# Breakout_Board.net
KiCad netlist of a schematic drawn in EAGLE
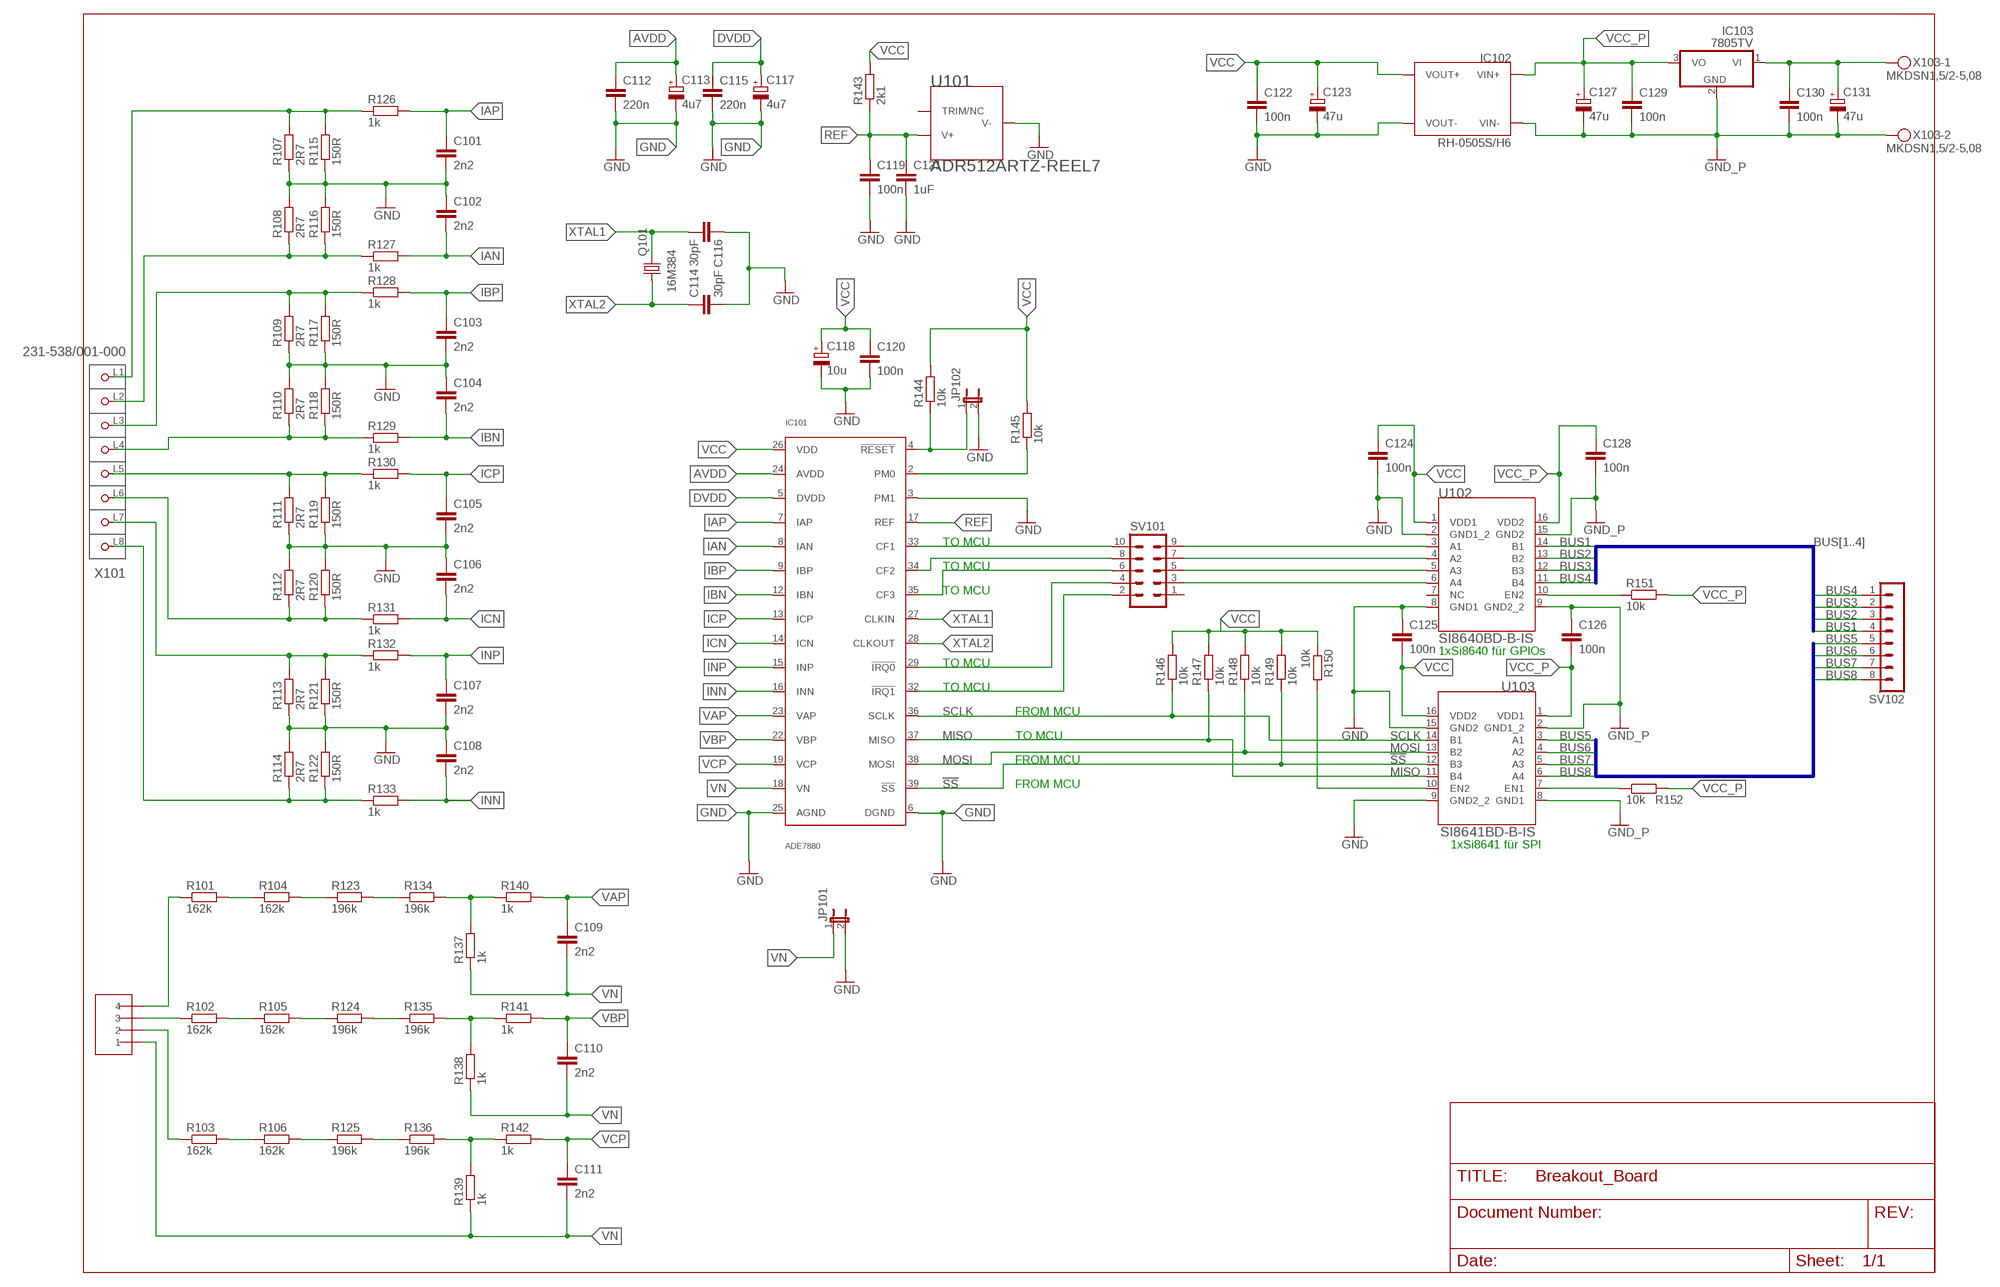
[diagram p0: schematic, sheet 1]

(export (version "E")
  (design (tool "Eeschema 10.0.6"))
  (components
    (comp (ref "C101")
      (value "2n2")
      (footprint "eagle-import:C0603K")
      (libsource (lib "eagle-import") (part "C-EUC0603K"))
    )
    (comp (ref "C102")
      (value "2n2")
      (footprint "eagle-import:C0603K")
      (libsource (lib "eagle-import") (part "C-EUC0603K"))
    )
    (comp (ref "C103")
      (value "2n2")
      (footprint "eagle-import:C0603K")
      (libsource (lib "eagle-import") (part "C-EUC0603K"))
    )
    (comp (ref "C104")
      (value "2n2")
      (footprint "eagle-import:C0603K")
      (libsource (lib "eagle-import") (part "C-EUC0603K"))
    )
    (comp (ref "C105")
      (value "2n2")
      (footprint "eagle-import:C0603K")
      (libsource (lib "eagle-import") (part "C-EUC0603K"))
    )
    (comp (ref "C106")
      (value "2n2")
      (footprint "eagle-import:C0603K")
      (libsource (lib "eagle-import") (part "C-EUC0603K"))
    )
    (comp (ref "C107")
      (value "2n2")
      (footprint "eagle-import:C0603K")
      (libsource (lib "eagle-import") (part "C-EUC0603K"))
    )
    (comp (ref "C108")
      (value "2n2")
      (footprint "eagle-import:C0603K")
      (libsource (lib "eagle-import") (part "C-EUC0603K"))
    )
    (comp (ref "C109")
      (value "2n2")
      (footprint "eagle-import:C0603K")
      (libsource (lib "eagle-import") (part "C-EUC0603K"))
    )
    (comp (ref "C110")
      (value "2n2")
      (footprint "eagle-import:C0603K")
      (libsource (lib "eagle-import") (part "C-EUC0603K"))
    )
    (comp (ref "C111")
      (value "2n2")
      (footprint "eagle-import:C0603K")
      (libsource (lib "eagle-import") (part "C-EUC0603K"))
    )
    (comp (ref "C112")
      (value "220n")
      (footprint "eagle-import:C0603K")
      (libsource (lib "eagle-import") (part "C-EUC0603K"))
    )
    (comp (ref "C113")
      (value "4u7")
      (footprint "eagle-import:PANASONIC_B")
      (libsource (lib "eagle-import") (part "CPOL-EUB"))
    )
    (comp (ref "C114")
      (value "30pF")
      (footprint "eagle-import:C0603K")
      (libsource (lib "eagle-import") (part "C-EUC0603K"))
    )
    (comp (ref "C115")
      (value "220n")
      (footprint "eagle-import:C0603K")
      (libsource (lib "eagle-import") (part "C-EUC0603K"))
    )
    (comp (ref "C116")
      (value "30pF")
      (footprint "eagle-import:C0603K")
      (libsource (lib "eagle-import") (part "C-EUC0603K"))
    )
    (comp (ref "C117")
      (value "4u7")
      (footprint "eagle-import:PANASONIC_B")
      (libsource (lib "eagle-import") (part "CPOL-EUB"))
    )
    (comp (ref "C118")
      (value "10u")
      (footprint "eagle-import:PANASONIC_B")
      (libsource (lib "eagle-import") (part "CPOL-EUB"))
    )
    (comp (ref "C119")
      (value "100n")
      (footprint "eagle-import:C0603K")
      (libsource (lib "eagle-import") (part "C-EUC0603K"))
    )
    (comp (ref "C120")
      (value "100n")
      (footprint "eagle-import:C0603K")
      (libsource (lib "eagle-import") (part "C-EUC0603K"))
    )
    (comp (ref "C121")
      (value "1uF")
      (footprint "eagle-import:C0603K")
      (libsource (lib "eagle-import") (part "C-EUC0603K"))
    )
    (comp (ref "C122")
      (value "100n")
      (footprint "eagle-import:C0603K")
      (libsource (lib "eagle-import") (part "C-EUC0603K"))
    )
    (comp (ref "C123")
      (value "47u")
      (footprint "eagle-import:PANASONIC_D")
      (libsource (lib "eagle-import") (part "CPOL-EUD"))
    )
    (comp (ref "C124")
      (value "100n")
      (footprint "eagle-import:C0603K")
      (libsource (lib "eagle-import") (part "C-EUC0603K"))
    )
    (comp (ref "C125")
      (value "100n")
      (footprint "eagle-import:C0603K")
      (libsource (lib "eagle-import") (part "C-EUC0603K"))
    )
    (comp (ref "C126")
      (value "100n")
      (footprint "eagle-import:C0603K")
      (libsource (lib "eagle-import") (part "C-EUC0603K"))
    )
    (comp (ref "C127")
      (value "47u")
      (footprint "eagle-import:PANASONIC_D")
      (libsource (lib "eagle-import") (part "CPOL-EUD"))
    )
    (comp (ref "C128")
      (value "100n")
      (footprint "eagle-import:C0603K")
      (libsource (lib "eagle-import") (part "C-EUC0603K"))
    )
    (comp (ref "C129")
      (value "100n")
      (footprint "eagle-import:C0603K")
      (libsource (lib "eagle-import") (part "C-EUC0603K"))
    )
    (comp (ref "C130")
      (value "100n")
      (footprint "eagle-import:C0603K")
      (libsource (lib "eagle-import") (part "C-EUC0603K"))
    )
    (comp (ref "C131")
      (value "47u")
      (footprint "eagle-import:PANASONIC_D")
      (libsource (lib "eagle-import") (part "CPOL-EUD"))
    )
    (comp (ref "IC101")
      (value "ADE7880")
      (footprint "eagle-import:BREAKOUT40P")
      (libsource (lib "eagle-import") (part "ADE7880"))
    )
    (comp (ref "IC102")
      (value "RH-0505S/H6")
      (footprint "eagle-import:RH_H6")
      (libsource (lib "eagle-import") (part "RH-0505S/H6"))
    )
    (comp (ref "IC103")
      (value "7805TV")
      (footprint "eagle-import:TO220V")
      (libsource (lib "eagle-import") (part "78TV05"))
    )
    (comp (ref "JP101")
      (value "JP1E")
      (footprint "eagle-import:JP1")
      (libsource (lib "eagle-import") (part "JP1E"))
    )
    (comp (ref "JP102")
      (value "JP1E")
      (footprint "eagle-import:JP1")
      (libsource (lib "eagle-import") (part "JP1E"))
    )
    (comp (ref "Q101")
      (value "16M384")
      (footprint "eagle-import:HC49UP")
      (libsource (lib "eagle-import") (part "CRYSTALHC49UP"))
    )
    (comp (ref "R101")
      (value "162k")
      (footprint "eagle-import:R0805")
      (libsource (lib "eagle-import") (part "R-EU_R0805"))
    )
    (comp (ref "R102")
      (value "162k")
      (footprint "eagle-import:R0805")
      (libsource (lib "eagle-import") (part "R-EU_R0805"))
    )
    (comp (ref "R103")
      (value "162k")
      (footprint "eagle-import:R0805")
      (libsource (lib "eagle-import") (part "R-EU_R0805"))
    )
    (comp (ref "R104")
      (value "162k")
      (footprint "eagle-import:R0805")
      (libsource (lib "eagle-import") (part "R-EU_R0805"))
    )
    (comp (ref "R105")
      (value "162k")
      (footprint "eagle-import:R0805")
      (libsource (lib "eagle-import") (part "R-EU_R0805"))
    )
    (comp (ref "R106")
      (value "162k")
      (footprint "eagle-import:R0805")
      (libsource (lib "eagle-import") (part "R-EU_R0805"))
    )
    (comp (ref "R107")
      (value "2R7")
      (footprint "eagle-import:R0805")
      (libsource (lib "eagle-import") (part "R-EU_R0805"))
    )
    (comp (ref "R108")
      (value "2R7")
      (footprint "eagle-import:R0805")
      (libsource (lib "eagle-import") (part "R-EU_R0805"))
    )
    (comp (ref "R109")
      (value "2R7")
      (footprint "eagle-import:R0805")
      (libsource (lib "eagle-import") (part "R-EU_R0805"))
    )
    (comp (ref "R110")
      (value "2R7")
      (footprint "eagle-import:R0805")
      (libsource (lib "eagle-import") (part "R-EU_R0805"))
    )
    (comp (ref "R111")
      (value "2R7")
      (footprint "eagle-import:R0805")
      (libsource (lib "eagle-import") (part "R-EU_R0805"))
    )
    (comp (ref "R112")
      (value "2R7")
      (footprint "eagle-import:R0805")
      (libsource (lib "eagle-import") (part "R-EU_R0805"))
    )
    (comp (ref "R113")
      (value "2R7")
      (footprint "eagle-import:R0805")
      (libsource (lib "eagle-import") (part "R-EU_R0805"))
    )
    (comp (ref "R114")
      (value "2R7")
      (footprint "eagle-import:R0805")
      (libsource (lib "eagle-import") (part "R-EU_R0805"))
    )
    (comp (ref "R115")
      (value "150R")
      (footprint "eagle-import:R0805")
      (libsource (lib "eagle-import") (part "R-EU_R0805"))
    )
    (comp (ref "R116")
      (value "150R")
      (footprint "eagle-import:R0805")
      (libsource (lib "eagle-import") (part "R-EU_R0805"))
    )
    (comp (ref "R117")
      (value "150R")
      (footprint "eagle-import:R0805")
      (libsource (lib "eagle-import") (part "R-EU_R0805"))
    )
    (comp (ref "R118")
      (value "150R")
      (footprint "eagle-import:R0805")
      (libsource (lib "eagle-import") (part "R-EU_R0805"))
    )
    (comp (ref "R119")
      (value "150R")
      (footprint "eagle-import:R0805")
      (libsource (lib "eagle-import") (part "R-EU_R0805"))
    )
    (comp (ref "R120")
      (value "150R")
      (footprint "eagle-import:R0805")
      (libsource (lib "eagle-import") (part "R-EU_R0805"))
    )
    (comp (ref "R121")
      (value "150R")
      (footprint "eagle-import:R0805")
      (libsource (lib "eagle-import") (part "R-EU_R0805"))
    )
    (comp (ref "R122")
      (value "150R")
      (footprint "eagle-import:R0805")
      (libsource (lib "eagle-import") (part "R-EU_R0805"))
    )
    (comp (ref "R123")
      (value "196k")
      (footprint "eagle-import:R0805")
      (libsource (lib "eagle-import") (part "R-EU_R0805"))
    )
    (comp (ref "R124")
      (value "196k")
      (footprint "eagle-import:R0805")
      (libsource (lib "eagle-import") (part "R-EU_R0805"))
    )
    (comp (ref "R125")
      (value "196k")
      (footprint "eagle-import:R0805")
      (libsource (lib "eagle-import") (part "R-EU_R0805"))
    )
    (comp (ref "R126")
      (value "1k")
      (footprint "eagle-import:R0603")
      (libsource (lib "eagle-import") (part "R-EU_R0603"))
    )
    (comp (ref "R127")
      (value "1k")
      (footprint "eagle-import:R0603")
      (libsource (lib "eagle-import") (part "R-EU_R0603"))
    )
    (comp (ref "R128")
      (value "1k")
      (footprint "eagle-import:R0603")
      (libsource (lib "eagle-import") (part "R-EU_R0603"))
    )
    (comp (ref "R129")
      (value "1k")
      (footprint "eagle-import:R0603")
      (libsource (lib "eagle-import") (part "R-EU_R0603"))
    )
    (comp (ref "R130")
      (value "1k")
      (footprint "eagle-import:R0603")
      (libsource (lib "eagle-import") (part "R-EU_R0603"))
    )
    (comp (ref "R131")
      (value "1k")
      (footprint "eagle-import:R0603")
      (libsource (lib "eagle-import") (part "R-EU_R0603"))
    )
    (comp (ref "R132")
      (value "1k")
      (footprint "eagle-import:R0603")
      (libsource (lib "eagle-import") (part "R-EU_R0603"))
    )
    (comp (ref "R133")
      (value "1k")
      (footprint "eagle-import:R0603")
      (libsource (lib "eagle-import") (part "R-EU_R0603"))
    )
    (comp (ref "R134")
      (value "196k")
      (footprint "eagle-import:R0805")
      (libsource (lib "eagle-import") (part "R-EU_R0805"))
    )
    (comp (ref "R135")
      (value "196k")
      (footprint "eagle-import:R0805")
      (libsource (lib "eagle-import") (part "R-EU_R0805"))
    )
    (comp (ref "R136")
      (value "196k")
      (footprint "eagle-import:R0805")
      (libsource (lib "eagle-import") (part "R-EU_R0805"))
    )
    (comp (ref "R137")
      (value "1k")
      (footprint "eagle-import:R0805")
      (libsource (lib "eagle-import") (part "R-EU_R0805"))
    )
    (comp (ref "R138")
      (value "1k")
      (footprint "eagle-import:R0805")
      (libsource (lib "eagle-import") (part "R-EU_R0805"))
    )
    (comp (ref "R139")
      (value "1k")
      (footprint "eagle-import:R0805")
      (libsource (lib "eagle-import") (part "R-EU_R0805"))
    )
    (comp (ref "R140")
      (value "1k")
      (footprint "eagle-import:R0603")
      (libsource (lib "eagle-import") (part "R-EU_R0603"))
    )
    (comp (ref "R141")
      (value "1k")
      (footprint "eagle-import:R0603")
      (libsource (lib "eagle-import") (part "R-EU_R0603"))
    )
    (comp (ref "R142")
      (value "1k")
      (footprint "eagle-import:R0603")
      (libsource (lib "eagle-import") (part "R-EU_R0603"))
    )
    (comp (ref "R143")
      (value "2k1")
      (footprint "eagle-import:R0603")
      (libsource (lib "eagle-import") (part "R-EU_R0603"))
    )
    (comp (ref "R144")
      (value "10k")
      (footprint "eagle-import:R0603")
      (libsource (lib "eagle-import") (part "R-EU_R0603"))
    )
    (comp (ref "R145")
      (value "10k")
      (footprint "eagle-import:R0603")
      (libsource (lib "eagle-import") (part "R-EU_R0603"))
    )
    (comp (ref "R146")
      (value "10k")
      (footprint "eagle-import:R0603")
      (libsource (lib "eagle-import") (part "R-EU_R0603"))
    )
    (comp (ref "R147")
      (value "10k")
      (footprint "eagle-import:R0603")
      (libsource (lib "eagle-import") (part "R-EU_R0603"))
    )
    (comp (ref "R148")
      (value "10k")
      (footprint "eagle-import:R0603")
      (libsource (lib "eagle-import") (part "R-EU_R0603"))
    )
    (comp (ref "R149")
      (value "10k")
      (footprint "eagle-import:R0603")
      (libsource (lib "eagle-import") (part "R-EU_R0603"))
    )
    (comp (ref "R150")
      (value "10k")
      (footprint "eagle-import:R0603")
      (libsource (lib "eagle-import") (part "R-EU_R0603"))
    )
    (comp (ref "R151")
      (value "10k")
      (footprint "eagle-import:R0603")
      (libsource (lib "eagle-import") (part "R-EU_R0603"))
    )
    (comp (ref "R152")
      (value "10k")
      (footprint "eagle-import:R0603")
      (libsource (lib "eagle-import") (part "R-EU_R0603"))
    )
    (comp (ref "SV101")
      (value "MA05-2")
      (footprint "eagle-import:MA05-2")
      (libsource (lib "eagle-import") (part "MA05-2"))
    )
    (comp (ref "SV102")
      (value "MA08-1")
      (footprint "eagle-import:MA08-1")
      (libsource (lib "eagle-import") (part "MA08-1"))
    )
    (comp (ref "U101")
      (value "ADR512ARTZ-REEL7")
      (footprint "eagle-import:RT_3")
      (libsource (lib "eagle-import") (part "ADR512ARTZ-REEL7"))
    )
    (comp (ref "U102")
      (value "SI8640BD-B-IS")
      (footprint "eagle-import:SOIC-16W")
      (libsource (lib "eagle-import") (part "SI8640BD-B-IS"))
    )
    (comp (ref "U103")
      (value "SI8641BD-B-IS")
      (footprint "eagle-import:SOIC-16W")
      (libsource (lib "eagle-import") (part "SI8641BD-B-IS"))
    )
    (comp (ref "X101")
      (value "231-538/001-000")
      (footprint "eagle-import:P-231-538_001-000")
      (libsource (lib "eagle-import") (part "231-538/001-000"))
    )
    (comp (ref "X102")
      (value "STL266-04")
      (footprint "eagle-import:7.62MM-4POL")
      (libsource (lib "eagle-import") (part "STL266-04"))
    )
    (comp (ref "X103")
      (value "MKDSN1,5/2-5,08")
      (footprint "eagle-import:MKDSN1,5_2-5,08")
      (libsource (lib "eagle-import") (part "MKDSN1,5/2-5,08"))
    )
  )
  (nets
    (net (code "1") (name "/BUS1") (class "Default")
      (node (ref "SV102") (pin "4") (pinfunction "4_4") (pintype "passive"))
      (node (ref "U102") (pin "14") (pinfunction "B1_14") (pintype "output"))
    )
    (net (code "2") (name "/BUS2") (class "Default")
      (node (ref "SV102") (pin "3") (pinfunction "3_3") (pintype "passive"))
      (node (ref "U102") (pin "13") (pinfunction "B2_13") (pintype "output"))
    )
    (net (code "3") (name "/BUS3") (class "Default")
      (node (ref "SV102") (pin "2") (pinfunction "2_2") (pintype "passive"))
      (node (ref "U102") (pin "12") (pinfunction "B3_12") (pintype "output"))
    )
    (net (code "4") (name "/BUS4") (class "Default")
      (node (ref "SV102") (pin "1") (pinfunction "1_1") (pintype "passive"))
      (node (ref "U102") (pin "11") (pinfunction "B4_11") (pintype "output"))
    )
    (net (code "5") (name "/BUS5") (class "Default")
      (node (ref "SV102") (pin "5") (pinfunction "5_5") (pintype "passive"))
      (node (ref "U103") (pin "3") (pinfunction "A1_3") (pintype "input"))
    )
    (net (code "6") (name "/BUS6") (class "Default")
      (node (ref "SV102") (pin "6") (pinfunction "6_6") (pintype "passive"))
      (node (ref "U103") (pin "4") (pinfunction "A2_4") (pintype "input"))
    )
    (net (code "7") (name "/BUS7") (class "Default")
      (node (ref "SV102") (pin "7") (pinfunction "7_7") (pintype "passive"))
      (node (ref "U103") (pin "5") (pinfunction "A3_5") (pintype "input"))
    )
    (net (code "8") (name "/BUS8") (class "Default")
      (node (ref "SV102") (pin "8") (pinfunction "8_8") (pintype "passive"))
      (node (ref "U103") (pin "6") (pinfunction "A4_6") (pintype "output"))
    )
    (net (code "10") (name "/MISO") (class "Default")
      (node (ref "IC101") (pin "37") (pinfunction "MISO_37") (pintype "bidirectional"))
      (node (ref "R147") (pin "1") (pinfunction "1_1") (pintype "passive"))
      (node (ref "U103") (pin "11") (pinfunction "B4_11") (pintype "input"))
    )
    (net (code "11") (name "/MOSI") (class "Default")
      (node (ref "IC101") (pin "38") (pinfunction "MOSI_38") (pintype "bidirectional"))
      (node (ref "R148") (pin "1") (pinfunction "1_1") (pintype "passive"))
      (node (ref "U103") (pin "13") (pinfunction "B2_13") (pintype "output"))
    )
    (net (code "12") (name "/SCLK") (class "Default")
      (node (ref "IC101") (pin "36") (pinfunction "SCLK_36") (pintype "bidirectional"))
      (node (ref "R146") (pin "1") (pinfunction "1_1") (pintype "passive"))
      (node (ref "U103") (pin "14") (pinfunction "B1_14") (pintype "output"))
    )
    (net (code "13") (name "/~{SS}") (class "Default")
      (node (ref "IC101") (pin "39") (pinfunction "~{SS}_39") (pintype "bidirectional"))
      (node (ref "R149") (pin "1") (pinfunction "1_1") (pintype "passive"))
      (node (ref "U103") (pin "12") (pinfunction "B3_12") (pintype "output"))
    )
    (net (code "14") (name "AVDD") (class "Default")
      (node (ref "C112") (pin "1") (pinfunction "1_1") (pintype "passive"))
      (node (ref "C113") (pin "+") (pinfunction "+_+") (pintype "passive"))
      (node (ref "IC101") (pin "24") (pinfunction "AVDD_24") (pintype "bidirectional"))
    )
    (net (code "15") (name "DVDD") (class "Default")
      (node (ref "C115") (pin "1") (pinfunction "1_1") (pintype "passive"))
      (node (ref "C117") (pin "+") (pinfunction "+_+") (pintype "passive"))
      (node (ref "IC101") (pin "5") (pinfunction "DVDD_5") (pintype "bidirectional"))
    )
    (net (code "16") (name "GND") (class "Default")
      (node (ref "C101") (pin "2") (pinfunction "2_2") (pintype "passive"))
      (node (ref "C102") (pin "1") (pinfunction "1_1") (pintype "passive"))
      (node (ref "C103") (pin "2") (pinfunction "2_2") (pintype "passive"))
      (node (ref "C104") (pin "1") (pinfunction "1_1") (pintype "passive"))
      (node (ref "C105") (pin "2") (pinfunction "2_2") (pintype "passive"))
      (node (ref "C106") (pin "1") (pinfunction "1_1") (pintype "passive"))
      (node (ref "C107") (pin "2") (pinfunction "2_2") (pintype "passive"))
      (node (ref "C108") (pin "1") (pinfunction "1_1") (pintype "passive"))
      (node (ref "C112") (pin "2") (pinfunction "2_2") (pintype "passive"))
      (node (ref "C113") (pin "-") (pinfunction "-_-") (pintype "passive"))
      (node (ref "C114") (pin "2") (pinfunction "2_2") (pintype "passive"))
      (node (ref "C115") (pin "2") (pinfunction "2_2") (pintype "passive"))
      (node (ref "C116") (pin "1") (pinfunction "1_1") (pintype "passive"))
      (node (ref "C117") (pin "-") (pinfunction "-_-") (pintype "passive"))
      (node (ref "C118") (pin "-") (pinfunction "-_-") (pintype "passive"))
      (node (ref "C119") (pin "2") (pinfunction "2_2") (pintype "passive"))
      (node (ref "C120") (pin "2") (pinfunction "2_2") (pintype "passive"))
      (node (ref "C121") (pin "2") (pinfunction "2_2") (pintype "passive"))
      (node (ref "C122") (pin "2") (pinfunction "2_2") (pintype "passive"))
      (node (ref "C123") (pin "-") (pinfunction "-_-") (pintype "passive"))
      (node (ref "C124") (pin "2") (pinfunction "2_2") (pintype "passive"))
      (node (ref "C125") (pin "1") (pinfunction "1_1") (pintype "passive"))
      (node (ref "IC101") (pin "25") (pinfunction "AGND_25") (pintype "bidirectional"))
      (node (ref "IC101") (pin "3") (pinfunction "PM1_3") (pintype "bidirectional"))
      (node (ref "IC101") (pin "6") (pinfunction "DGND_6") (pintype "bidirectional"))
      (node (ref "IC102") (pin "P$3") (pinfunction "VOUT-_P$3") (pintype "bidirectional"))
      (node (ref "JP101") (pin "2") (pinfunction "2_2") (pintype "passive"))
      (node (ref "JP102") (pin "2") (pinfunction "2_2") (pintype "passive"))
      (node (ref "R107") (pin "1") (pinfunction "1_1") (pintype "passive"))
      (node (ref "R108") (pin "2") (pinfunction "2_2") (pintype "passive"))
      (node (ref "R109") (pin "1") (pinfunction "1_1") (pintype "passive"))
      (node (ref "R110") (pin "2") (pinfunction "2_2") (pintype "passive"))
      (node (ref "R111") (pin "1") (pinfunction "1_1") (pintype "passive"))
      (node (ref "R112") (pin "2") (pinfunction "2_2") (pintype "passive"))
      (node (ref "R113") (pin "1") (pinfunction "1_1") (pintype "passive"))
      (node (ref "R114") (pin "2") (pinfunction "2_2") (pintype "passive"))
      (node (ref "R115") (pin "1") (pinfunction "1_1") (pintype "passive"))
      (node (ref "R116") (pin "2") (pinfunction "2_2") (pintype "passive"))
      (node (ref "R117") (pin "1") (pinfunction "1_1") (pintype "passive"))
      (node (ref "R118") (pin "2") (pinfunction "2_2") (pintype "passive"))
      (node (ref "R119") (pin "1") (pinfunction "1_1") (pintype "passive"))
      (node (ref "R120") (pin "2") (pinfunction "2_2") (pintype "passive"))
      (node (ref "R121") (pin "1") (pinfunction "1_1") (pintype "passive"))
      (node (ref "R122") (pin "2") (pinfunction "2_2") (pintype "passive"))
      (node (ref "U101") (pin "2") (pinfunction "V-_2") (pintype "power_in"))
      (node (ref "U102") (pin "2") (pinfunction "GND1_2_2") (pintype "passive"))
      (node (ref "U102") (pin "8") (pinfunction "GND1_8") (pintype "passive"))
      (node (ref "U103") (pin "15") (pinfunction "GND2_15") (pintype "passive"))
      (node (ref "U103") (pin "9") (pinfunction "GND2_2_9") (pintype "passive"))
    )
    (net (code "17") (name "GND_P") (class "Default")
      (node (ref "C126") (pin "1") (pinfunction "1_1") (pintype "passive"))
      (node (ref "C127") (pin "-") (pinfunction "-_-") (pintype "passive"))
      (node (ref "C128") (pin "2") (pinfunction "2_2") (pintype "passive"))
      (node (ref "C129") (pin "2") (pinfunction "2_2") (pintype "passive"))
      (node (ref "C130") (pin "2") (pinfunction "2_2") (pintype "passive"))
      (node (ref "C131") (pin "-") (pinfunction "-_-") (pintype "passive"))
      (node (ref "IC102") (pin "P$2") (pinfunction "VIN-_P$2") (pintype "bidirectional"))
      (node (ref "IC103") (pin "2") (pinfunction "GND_2") (pintype "passive"))
      (node (ref "U102") (pin "15") (pinfunction "GND2_15") (pintype "passive"))
      (node (ref "U102") (pin "9") (pinfunction "GND2_2_9") (pintype "passive"))
      (node (ref "U103") (pin "2") (pinfunction "GND1_2_2") (pintype "passive"))
      (node (ref "U103") (pin "8") (pinfunction "GND1_8") (pintype "passive"))
      (node (ref "X103") (pin "2") (pinfunction "KL_2") (pintype "passive"))
    )
    (net (code "18") (name "IAN") (class "Default")
      (node (ref "C102") (pin "2") (pinfunction "2_2") (pintype "passive"))
      (node (ref "IC101") (pin "8") (pinfunction "IAN_8") (pintype "bidirectional"))
      (node (ref "R127") (pin "2") (pinfunction "2_2") (pintype "passive"))
    )
    (net (code "19") (name "IAP") (class "Default")
      (node (ref "C101") (pin "1") (pinfunction "1_1") (pintype "passive"))
      (node (ref "IC101") (pin "7") (pinfunction "IAP_7") (pintype "bidirectional"))
      (node (ref "R126") (pin "2") (pinfunction "2_2") (pintype "passive"))
    )
    (net (code "20") (name "IBN") (class "Default")
      (node (ref "C104") (pin "2") (pinfunction "2_2") (pintype "passive"))
      (node (ref "IC101") (pin "12") (pinfunction "IBN_12") (pintype "bidirectional"))
      (node (ref "R129") (pin "2") (pinfunction "2_2") (pintype "passive"))
    )
    (net (code "21") (name "IBP") (class "Default")
      (node (ref "C103") (pin "1") (pinfunction "1_1") (pintype "passive"))
      (node (ref "IC101") (pin "9") (pinfunction "IBP_9") (pintype "bidirectional"))
      (node (ref "R128") (pin "2") (pinfunction "2_2") (pintype "passive"))
    )
    (net (code "22") (name "ICN") (class "Default")
      (node (ref "C106") (pin "2") (pinfunction "2_2") (pintype "passive"))
      (node (ref "IC101") (pin "14") (pinfunction "ICN_14") (pintype "bidirectional"))
      (node (ref "R131") (pin "2") (pinfunction "2_2") (pintype "passive"))
    )
    (net (code "23") (name "ICP") (class "Default")
      (node (ref "C105") (pin "1") (pinfunction "1_1") (pintype "passive"))
      (node (ref "IC101") (pin "13") (pinfunction "ICP_13") (pintype "bidirectional"))
      (node (ref "R130") (pin "2") (pinfunction "2_2") (pintype "passive"))
    )
    (net (code "24") (name "INN") (class "Default")
      (node (ref "C108") (pin "2") (pinfunction "2_2") (pintype "passive"))
      (node (ref "IC101") (pin "16") (pinfunction "INN_16") (pintype "bidirectional"))
      (node (ref "R133") (pin "2") (pinfunction "2_2") (pintype "passive"))
    )
    (net (code "25") (name "INP") (class "Default")
      (node (ref "C107") (pin "1") (pinfunction "1_1") (pintype "passive"))
      (node (ref "IC101") (pin "15") (pinfunction "INP_15") (pintype "bidirectional"))
      (node (ref "R132") (pin "2") (pinfunction "2_2") (pintype "passive"))
    )
    (net (code "26") (name "Net-(IC101-CF1)") (class "Default")
      (node (ref "IC101") (pin "33") (pinfunction "CF1_33") (pintype "bidirectional"))
      (node (ref "SV101") (pin "10") (pinfunction "10_10") (pintype "passive"))
    )
    (net (code "27") (name "Net-(IC101-CF2)") (class "Default")
      (node (ref "IC101") (pin "34") (pinfunction "CF2_34") (pintype "bidirectional"))
      (node (ref "SV101") (pin "8") (pinfunction "8_8") (pintype "passive"))
    )
    (net (code "28") (name "Net-(IC101-CF3)") (class "Default")
      (node (ref "IC101") (pin "35") (pinfunction "CF3_35") (pintype "bidirectional"))
      (node (ref "SV101") (pin "6") (pinfunction "6_6") (pintype "passive"))
    )
    (net (code "29") (name "Net-(IC101-PM0)") (class "Default")
      (node (ref "IC101") (pin "2") (pinfunction "PM0_2") (pintype "bidirectional"))
      (node (ref "R145") (pin "1") (pinfunction "1_1") (pintype "passive"))
    )
    (net (code "30") (name "Net-(IC101-~{IRQ0})") (class "Default")
      (node (ref "IC101") (pin "29") (pinfunction "~{IRQ0}_29") (pintype "bidirectional"))
      (node (ref "SV101") (pin "4") (pinfunction "4_4") (pintype "passive"))
    )
    (net (code "31") (name "Net-(IC101-~{IRQ1})") (class "Default")
      (node (ref "IC101") (pin "32") (pinfunction "~{IRQ1}_32") (pintype "bidirectional"))
      (node (ref "SV101") (pin "2") (pinfunction "2_2") (pintype "passive"))
    )
    (net (code "32") (name "Net-(IC101-~{RESET})") (class "Default")
      (node (ref "IC101") (pin "4") (pinfunction "~{RESET}_4") (pintype "bidirectional"))
      (node (ref "JP102") (pin "1") (pinfunction "1_1") (pintype "passive"))
      (node (ref "R144") (pin "1") (pinfunction "1_1") (pintype "passive"))
    )
    (net (code "33") (name "Net-(IC103-VI)") (class "Default")
      (node (ref "C130") (pin "1") (pinfunction "1_1") (pintype "passive"))
      (node (ref "C131") (pin "+") (pinfunction "+_+") (pintype "passive"))
      (node (ref "IC103") (pin "1") (pinfunction "VI_1") (pintype "input"))
      (node (ref "X103") (pin "1") (pinfunction "KL_1") (pintype "passive"))
    )
    (net (code "34") (name "Net-(R101-Pad2)") (class "Default")
      (node (ref "R101") (pin "2") (pinfunction "2_2") (pintype "passive"))
      (node (ref "R104") (pin "1") (pinfunction "1_1") (pintype "passive"))
    )
    (net (code "35") (name "Net-(R102-Pad2)") (class "Default")
      (node (ref "R102") (pin "2") (pinfunction "2_2") (pintype "passive"))
      (node (ref "R105") (pin "1") (pinfunction "1_1") (pintype "passive"))
    )
    (net (code "36") (name "Net-(R103-Pad2)") (class "Default")
      (node (ref "R103") (pin "2") (pinfunction "2_2") (pintype "passive"))
      (node (ref "R106") (pin "1") (pinfunction "1_1") (pintype "passive"))
    )
    (net (code "37") (name "Net-(R104-Pad2)") (class "Default")
      (node (ref "R104") (pin "2") (pinfunction "2_2") (pintype "passive"))
      (node (ref "R123") (pin "1") (pinfunction "1_1") (pintype "passive"))
    )
    (net (code "38") (name "Net-(R105-Pad2)") (class "Default")
      (node (ref "R105") (pin "2") (pinfunction "2_2") (pintype "passive"))
      (node (ref "R124") (pin "1") (pinfunction "1_1") (pintype "passive"))
    )
    (net (code "39") (name "Net-(R106-Pad2)") (class "Default")
      (node (ref "R106") (pin "2") (pinfunction "2_2") (pintype "passive"))
      (node (ref "R125") (pin "1") (pinfunction "1_1") (pintype "passive"))
    )
    (net (code "40") (name "Net-(R123-Pad2)") (class "Default")
      (node (ref "R123") (pin "2") (pinfunction "2_2") (pintype "passive"))
      (node (ref "R134") (pin "1") (pinfunction "1_1") (pintype "passive"))
    )
    (net (code "41") (name "Net-(R124-Pad2)") (class "Default")
      (node (ref "R124") (pin "2") (pinfunction "2_2") (pintype "passive"))
      (node (ref "R135") (pin "1") (pinfunction "1_1") (pintype "passive"))
    )
    (net (code "42") (name "Net-(R125-Pad2)") (class "Default")
      (node (ref "R125") (pin "2") (pinfunction "2_2") (pintype "passive"))
      (node (ref "R136") (pin "1") (pinfunction "1_1") (pintype "passive"))
    )
    (net (code "43") (name "Net-(R134-Pad2)") (class "Default")
      (node (ref "R134") (pin "2") (pinfunction "2_2") (pintype "passive"))
      (node (ref "R137") (pin "2") (pinfunction "2_2") (pintype "passive"))
      (node (ref "R140") (pin "1") (pinfunction "1_1") (pintype "passive"))
    )
    (net (code "44") (name "Net-(R135-Pad2)") (class "Default")
      (node (ref "R135") (pin "2") (pinfunction "2_2") (pintype "passive"))
      (node (ref "R138") (pin "2") (pinfunction "2_2") (pintype "passive"))
      (node (ref "R141") (pin "1") (pinfunction "1_1") (pintype "passive"))
    )
    (net (code "45") (name "Net-(R136-Pad2)") (class "Default")
      (node (ref "R136") (pin "2") (pinfunction "2_2") (pintype "passive"))
      (node (ref "R139") (pin "2") (pinfunction "2_2") (pintype "passive"))
      (node (ref "R142") (pin "1") (pinfunction "1_1") (pintype "passive"))
    )
    (net (code "46") (name "Net-(U102-A1)") (class "Default")
      (node (ref "SV101") (pin "9") (pinfunction "9_9") (pintype "passive"))
      (node (ref "U102") (pin "3") (pinfunction "A1_3") (pintype "input"))
    )
    (net (code "47") (name "Net-(U102-A2)") (class "Default")
      (node (ref "SV101") (pin "7") (pinfunction "7_7") (pintype "passive"))
      (node (ref "U102") (pin "4") (pinfunction "A2_4") (pintype "input"))
    )
    (net (code "48") (name "Net-(U102-A3)") (class "Default")
      (node (ref "SV101") (pin "5") (pinfunction "5_5") (pintype "passive"))
      (node (ref "U102") (pin "5") (pinfunction "A3_5") (pintype "input"))
    )
    (net (code "49") (name "Net-(U102-A4)") (class "Default")
      (node (ref "SV101") (pin "3") (pinfunction "3_3") (pintype "passive"))
      (node (ref "U102") (pin "6") (pinfunction "A4_6") (pintype "input"))
    )
    (net (code "50") (name "Net-(U102-EN2)") (class "Default")
      (node (ref "R151") (pin "1") (pinfunction "1_1") (pintype "passive"))
      (node (ref "U102") (pin "10") (pinfunction "EN2_10") (pintype "input"))
    )
    (net (code "51") (name "Net-(U103-EN1)") (class "Default")
      (node (ref "R152") (pin "1") (pinfunction "1_1") (pintype "passive"))
      (node (ref "U103") (pin "7") (pinfunction "EN1_7") (pintype "input"))
    )
    (net (code "52") (name "Net-(U103-EN2)") (class "Default")
      (node (ref "R150") (pin "2") (pinfunction "2_2") (pintype "passive"))
      (node (ref "U103") (pin "10") (pinfunction "EN2_10") (pintype "input"))
    )
    (net (code "53") (name "Net-(X101-P1)") (class "Default")
      (node (ref "R107") (pin "2") (pinfunction "2_2") (pintype "passive"))
      (node (ref "R115") (pin "2") (pinfunction "2_2") (pintype "passive"))
      (node (ref "R126") (pin "1") (pinfunction "1_1") (pintype "passive"))
      (node (ref "X101") (pin "L1") (pinfunction "P1_L1") (pintype "bidirectional"))
    )
    (net (code "54") (name "Net-(X101-P2)") (class "Default")
      (node (ref "R108") (pin "1") (pinfunction "1_1") (pintype "passive"))
      (node (ref "R116") (pin "1") (pinfunction "1_1") (pintype "passive"))
      (node (ref "R127") (pin "1") (pinfunction "1_1") (pintype "passive"))
      (node (ref "X101") (pin "L2") (pinfunction "P2_L2") (pintype "bidirectional"))
    )
    (net (code "55") (name "Net-(X101-P3)") (class "Default")
      (node (ref "R109") (pin "2") (pinfunction "2_2") (pintype "passive"))
      (node (ref "R117") (pin "2") (pinfunction "2_2") (pintype "passive"))
      (node (ref "R128") (pin "1") (pinfunction "1_1") (pintype "passive"))
      (node (ref "X101") (pin "L3") (pinfunction "P3_L3") (pintype "bidirectional"))
    )
    (net (code "56") (name "Net-(X101-P4)") (class "Default")
      (node (ref "R110") (pin "1") (pinfunction "1_1") (pintype "passive"))
      (node (ref "R118") (pin "1") (pinfunction "1_1") (pintype "passive"))
      (node (ref "R129") (pin "1") (pinfunction "1_1") (pintype "passive"))
      (node (ref "X101") (pin "L4") (pinfunction "P4_L4") (pintype "bidirectional"))
    )
    (net (code "57") (name "Net-(X101-P5)") (class "Default")
      (node (ref "R111") (pin "2") (pinfunction "2_2") (pintype "passive"))
      (node (ref "R119") (pin "2") (pinfunction "2_2") (pintype "passive"))
      (node (ref "R130") (pin "1") (pinfunction "1_1") (pintype "passive"))
      (node (ref "X101") (pin "L5") (pinfunction "P5_L5") (pintype "bidirectional"))
    )
    (net (code "58") (name "Net-(X101-P6)") (class "Default")
      (node (ref "R112") (pin "1") (pinfunction "1_1") (pintype "passive"))
      (node (ref "R120") (pin "1") (pinfunction "1_1") (pintype "passive"))
      (node (ref "R131") (pin "1") (pinfunction "1_1") (pintype "passive"))
      (node (ref "X101") (pin "L6") (pinfunction "P6_L6") (pintype "bidirectional"))
    )
    (net (code "59") (name "Net-(X101-P7)") (class "Default")
      (node (ref "R113") (pin "2") (pinfunction "2_2") (pintype "passive"))
      (node (ref "R121") (pin "2") (pinfunction "2_2") (pintype "passive"))
      (node (ref "R132") (pin "1") (pinfunction "1_1") (pintype "passive"))
      (node (ref "X101") (pin "L7") (pinfunction "P7_L7") (pintype "bidirectional"))
    )
    (net (code "60") (name "Net-(X101-P8)") (class "Default")
      (node (ref "R114") (pin "1") (pinfunction "1_1") (pintype "passive"))
      (node (ref "R122") (pin "1") (pinfunction "1_1") (pintype "passive"))
      (node (ref "R133") (pin "1") (pinfunction "1_1") (pintype "passive"))
      (node (ref "X101") (pin "L8") (pinfunction "P8_L8") (pintype "bidirectional"))
    )
    (net (code "61") (name "Net-(X102-2)") (class "Default")
      (node (ref "R103") (pin "1") (pinfunction "1_1") (pintype "passive"))
      (node (ref "X102") (pin "P$2") (pinfunction "2_P$2") (pintype "bidirectional"))
    )
    (net (code "62") (name "Net-(X102-3)") (class "Default")
      (node (ref "R102") (pin "1") (pinfunction "1_1") (pintype "passive"))
      (node (ref "X102") (pin "P$3") (pinfunction "3_P$3") (pintype "bidirectional"))
    )
    (net (code "63") (name "Net-(X102-4)") (class "Default")
      (node (ref "R101") (pin "1") (pinfunction "1_1") (pintype "passive"))
      (node (ref "X102") (pin "P$4") (pinfunction "4_P$4") (pintype "bidirectional"))
    )
    (net (code "64") (name "REF") (class "Default")
      (node (ref "C119") (pin "1") (pinfunction "1_1") (pintype "passive"))
      (node (ref "C121") (pin "1") (pinfunction "1_1") (pintype "passive"))
      (node (ref "IC101") (pin "17") (pinfunction "REF_17") (pintype "bidirectional"))
      (node (ref "R143") (pin "1") (pinfunction "1_1") (pintype "passive"))
      (node (ref "U101") (pin "1") (pinfunction "V+_1") (pintype "power_in"))
    )
    (net (code "65") (name "VAP") (class "Default")
      (node (ref "C109") (pin "1") (pinfunction "1_1") (pintype "passive"))
      (node (ref "IC101") (pin "23") (pinfunction "VAP_23") (pintype "bidirectional"))
      (node (ref "R140") (pin "2") (pinfunction "2_2") (pintype "passive"))
    )
    (net (code "66") (name "VBP") (class "Default")
      (node (ref "C110") (pin "1") (pinfunction "1_1") (pintype "passive"))
      (node (ref "IC101") (pin "22") (pinfunction "VBP_22") (pintype "bidirectional"))
      (node (ref "R141") (pin "2") (pinfunction "2_2") (pintype "passive"))
    )
    (net (code "67") (name "VCC") (class "Default")
      (node (ref "C118") (pin "+") (pinfunction "+_+") (pintype "passive"))
      (node (ref "C120") (pin "1") (pinfunction "1_1") (pintype "passive"))
      (node (ref "C122") (pin "1") (pinfunction "1_1") (pintype "passive"))
      (node (ref "C123") (pin "+") (pinfunction "+_+") (pintype "passive"))
      (node (ref "C124") (pin "1") (pinfunction "1_1") (pintype "passive"))
      (node (ref "C125") (pin "2") (pinfunction "2_2") (pintype "passive"))
      (node (ref "IC101") (pin "26") (pinfunction "VDD_26") (pintype "bidirectional"))
      (node (ref "IC102") (pin "P$5") (pinfunction "VOUT+_P$5") (pintype "bidirectional"))
      (node (ref "R143") (pin "2") (pinfunction "2_2") (pintype "passive"))
      (node (ref "R144") (pin "2") (pinfunction "2_2") (pintype "passive"))
      (node (ref "R145") (pin "2") (pinfunction "2_2") (pintype "passive"))
      (node (ref "R146") (pin "2") (pinfunction "2_2") (pintype "passive"))
      (node (ref "R147") (pin "2") (pinfunction "2_2") (pintype "passive"))
      (node (ref "R148") (pin "2") (pinfunction "2_2") (pintype "passive"))
      (node (ref "R149") (pin "2") (pinfunction "2_2") (pintype "passive"))
      (node (ref "R150") (pin "1") (pinfunction "1_1") (pintype "passive"))
      (node (ref "U102") (pin "1") (pinfunction "VDD1_1") (pintype "passive"))
      (node (ref "U103") (pin "16") (pinfunction "VDD2_16") (pintype "passive"))
    )
    (net (code "68") (name "VCC_P") (class "Default")
      (node (ref "C126") (pin "2") (pinfunction "2_2") (pintype "passive"))
      (node (ref "C127") (pin "+") (pinfunction "+_+") (pintype "passive"))
      (node (ref "C128") (pin "1") (pinfunction "1_1") (pintype "passive"))
      (node (ref "C129") (pin "1") (pinfunction "1_1") (pintype "passive"))
      (node (ref "IC102") (pin "P$1") (pinfunction "VIN+_P$1") (pintype "bidirectional"))
      (node (ref "IC103") (pin "3") (pinfunction "VO_3") (pintype "passive"))
      (node (ref "R151") (pin "2") (pinfunction "2_2") (pintype "passive"))
      (node (ref "R152") (pin "2") (pinfunction "2_2") (pintype "passive"))
      (node (ref "U102") (pin "16") (pinfunction "VDD2_16") (pintype "passive"))
      (node (ref "U103") (pin "1") (pinfunction "VDD1_1") (pintype "passive"))
    )
    (net (code "69") (name "VCP") (class "Default")
      (node (ref "C111") (pin "1") (pinfunction "1_1") (pintype "passive"))
      (node (ref "IC101") (pin "19") (pinfunction "VCP_19") (pintype "bidirectional"))
      (node (ref "R142") (pin "2") (pinfunction "2_2") (pintype "passive"))
    )
    (net (code "70") (name "VN") (class "Default")
      (node (ref "C109") (pin "2") (pinfunction "2_2") (pintype "passive"))
      (node (ref "C110") (pin "2") (pinfunction "2_2") (pintype "passive"))
      (node (ref "C111") (pin "2") (pinfunction "2_2") (pintype "passive"))
      (node (ref "IC101") (pin "18") (pinfunction "VN_18") (pintype "bidirectional"))
      (node (ref "JP101") (pin "1") (pinfunction "1_1") (pintype "passive"))
      (node (ref "R137") (pin "1") (pinfunction "1_1") (pintype "passive"))
      (node (ref "R138") (pin "1") (pinfunction "1_1") (pintype "passive"))
      (node (ref "R139") (pin "1") (pinfunction "1_1") (pintype "passive"))
      (node (ref "X102") (pin "P$1") (pinfunction "1_P$1") (pintype "bidirectional"))
    )
    (net (code "71") (name "XTAL1") (class "Default")
      (node (ref "C116") (pin "2") (pinfunction "2_2") (pintype "passive"))
      (node (ref "IC101") (pin "27") (pinfunction "CLKIN_27") (pintype "bidirectional"))
      (node (ref "Q101") (pin "2") (pinfunction "2_2") (pintype "passive"))
    )
    (net (code "72") (name "XTAL2") (class "Default")
      (node (ref "C114") (pin "1") (pinfunction "1_1") (pintype "passive"))
      (node (ref "IC101") (pin "28") (pinfunction "CLKOUT_28") (pintype "bidirectional"))
      (node (ref "Q101") (pin "1") (pinfunction "1_1") (pintype "passive"))
    )
    (net (code "73") (name "unconnected-(SV101-Pad1)") (class "Default")
      (node (ref "SV101") (pin "1") (pinfunction "1_1") (pintype "passive"))
    )
    (net (code "74") (name "unconnected-(U101-TRIM{slash}NC-Pad3)") (class "Default")
      (node (ref "U101") (pin "3") (pinfunction "TRIM/NC_3") (pintype "passive"))
    )
    (net (code "75") (name "unconnected-(U102-NC-Pad7)") (class "Default")
      (node (ref "U102") (pin "7") (pinfunction "NC_7") (pintype "no_connect"))
    )
  )
)
